# 468323_001_Connectors.net
KiCad netlist of a schematic drawn in Altium Designer
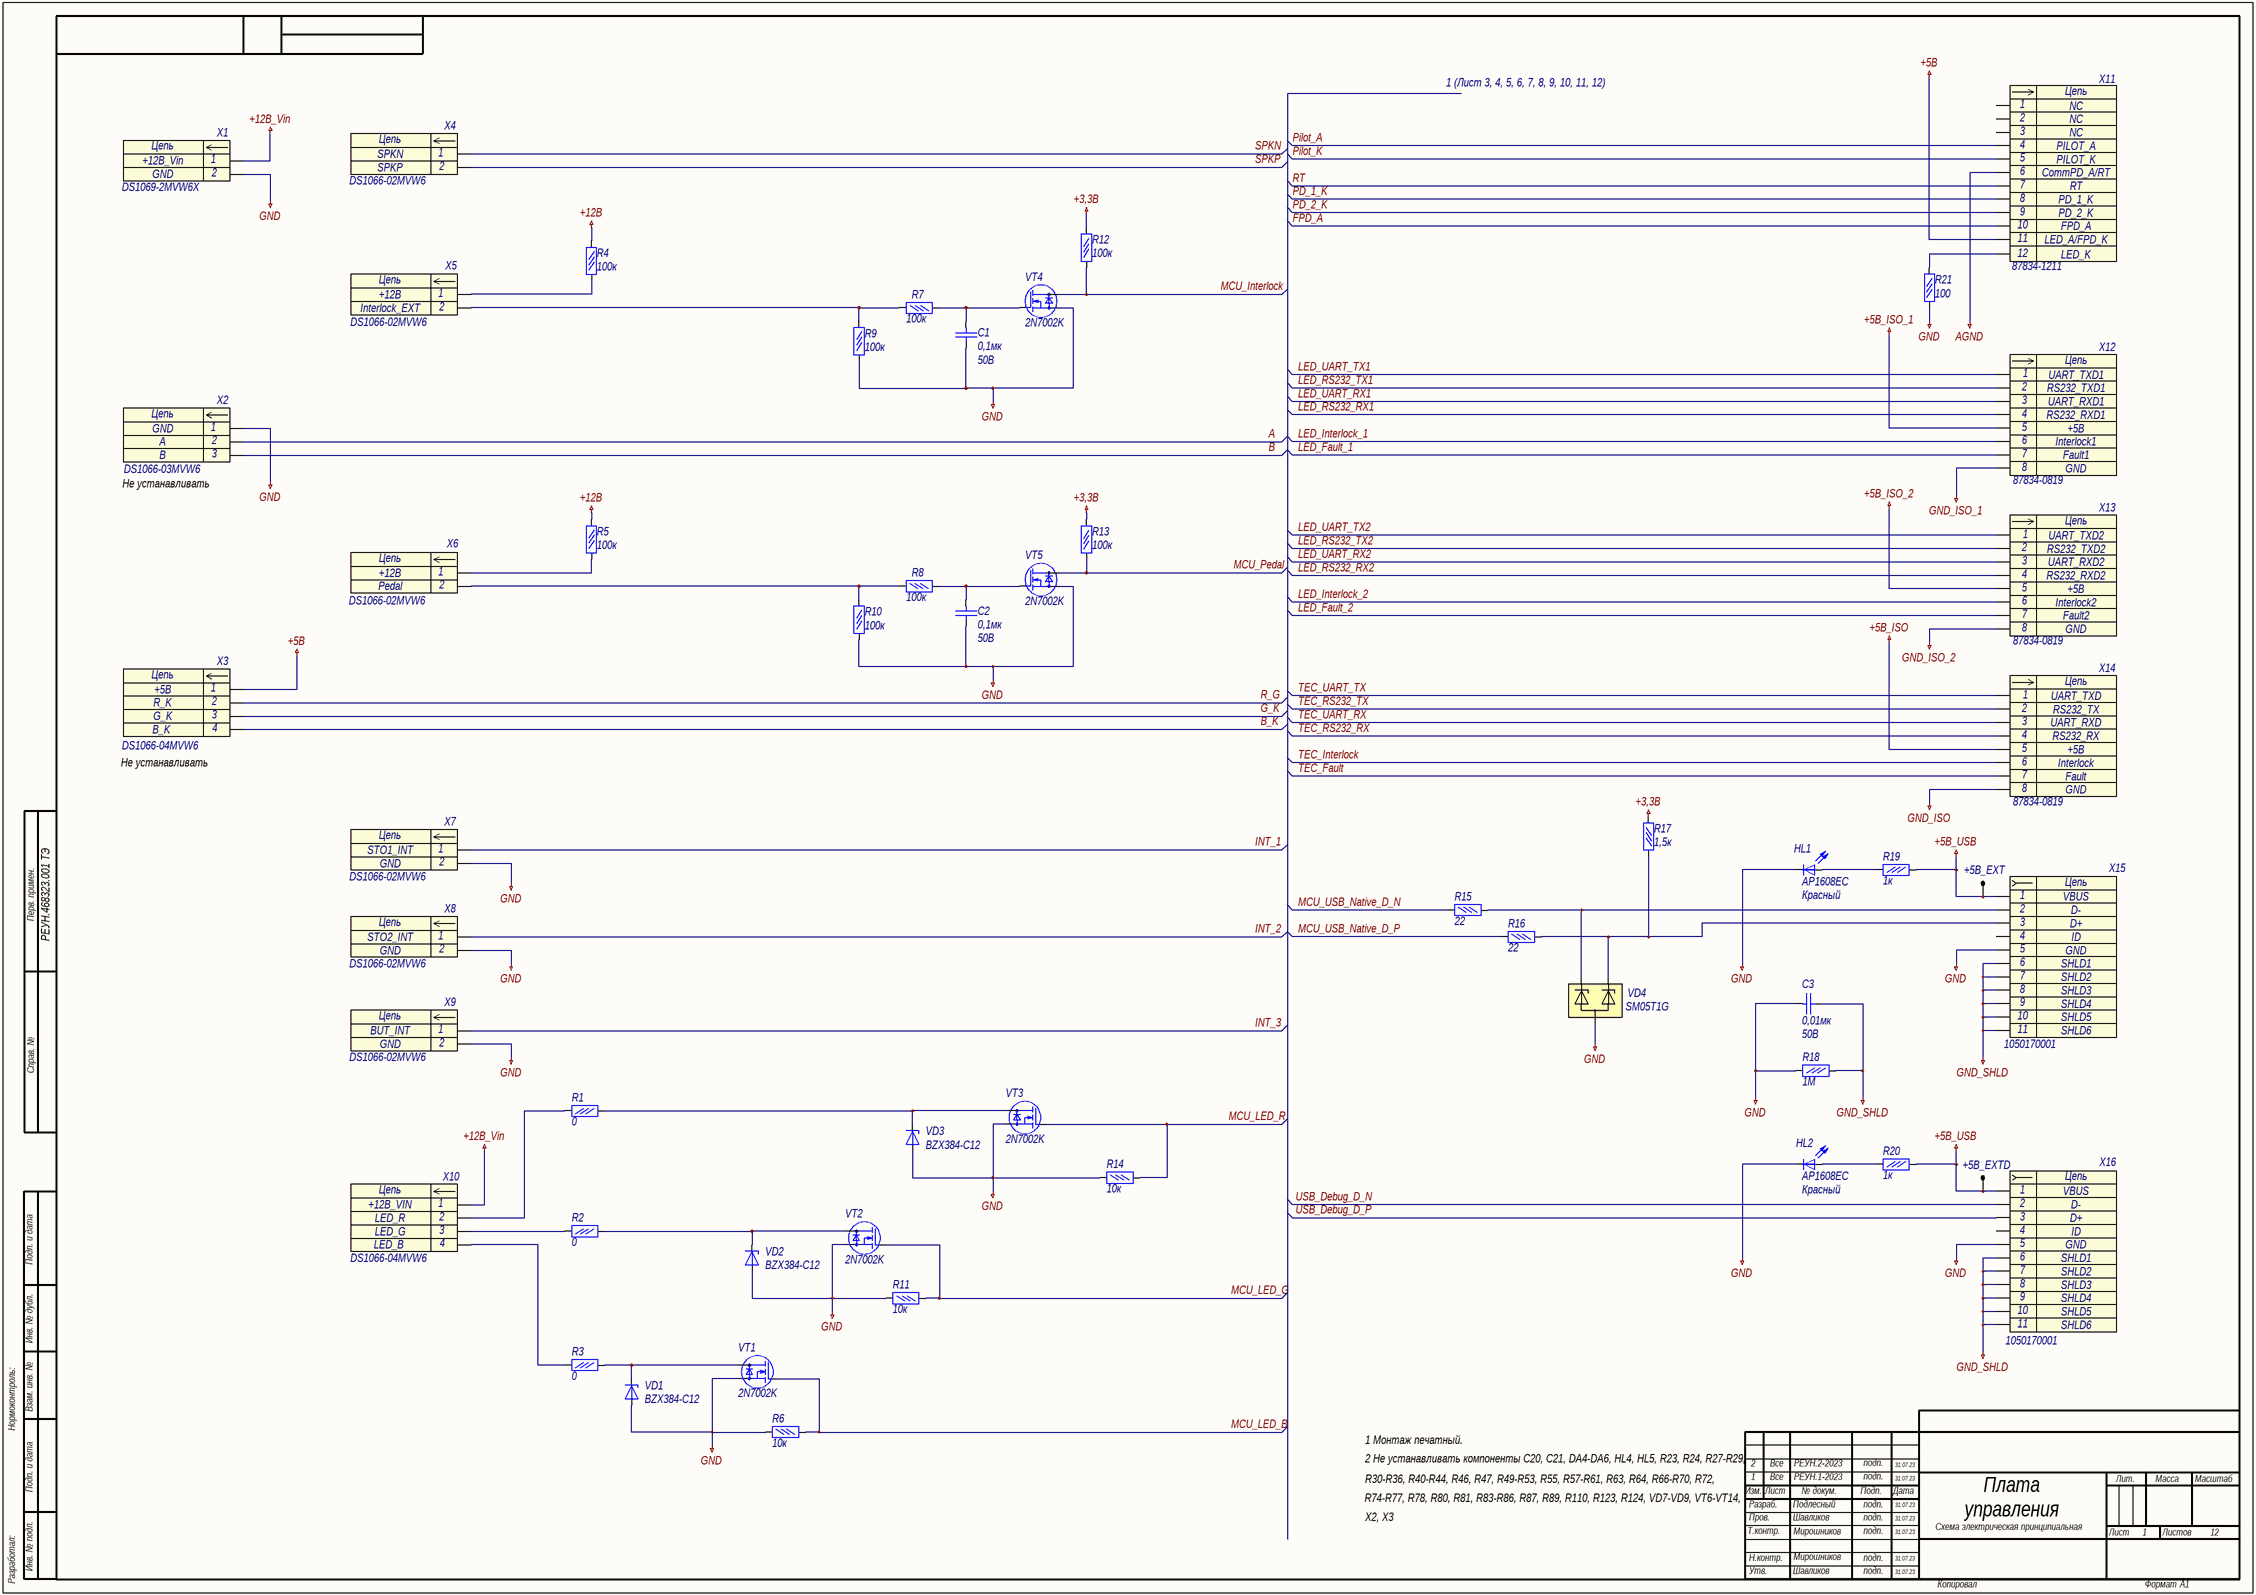
[diagram p0: РЕУН.468323.001_Connectors.SchDoc]

(export (version "E")
  (design (tool "Eeschema 10.0.6"))
  (components
    (comp (ref "+5В_EXT")
      (value "\"1\"")
      (footprint "0.5 x 1_round")
      (description "Test point")
      (libsource (lib "TarabusLib_KOR") (part "TestPoint"))
    )
    (comp (ref "+5В_EXTD")
      (value "\"1\"")
      (footprint "0.5 x 1_round")
      (description "Test point")
      (libsource (lib "TarabusLib_KOR") (part "TestPoint"))
    )
    (comp (ref "C1")
      (value "0,1мк")
      (footprint "C0805_AA")
      (description "Конденсатор кер.")
      (fields (field (name "VOLTAGE") "50В"))
      (libsource (lib "Library_Diana") (part "Конденсатор кер."))
    )
    (comp (ref "C2")
      (value "0,1мк")
      (footprint "C0805_AA")
      (description "Конденсатор кер.")
      (fields (field (name "VOLTAGE") "50В"))
      (libsource (lib "Library_Diana") (part "Конденсатор кер."))
    )
    (comp (ref "C3")
      (value "0,01мк")
      (footprint "C0805_AA")
      (description "Конденсатор кер.")
      (fields (field (name "VOLTAGE") "50В"))
      (libsource (lib "Library_Diana") (part "Конденсатор кер."))
    )
    (comp (ref "HL1")
      (value "AP1608EC")
      (description "Светодиод")
      (fields (field (name "NAME") "AP1608EC") (field (name "COLOR") "Красный"))
      (libsource (lib "Library_Diana") (part "led"))
    )
    (comp (ref "HL2")
      (value "AP1608EC")
      (description "Светодиод")
      (fields (field (name "NAME") "AP1608EC") (field (name "COLOR") "Красный"))
      (libsource (lib "Library_Diana") (part "led"))
    )
    (comp (ref "R1")
      (value "0")
      (footprint "R1206")
      (description "Резистор 0,05Вт")
      (libsource (lib "") (part "Резистор  0,05Вт_2"))
    )
    (comp (ref "R2")
      (value "0")
      (footprint "R1206")
      (description "Резистор 0,05Вт")
      (libsource (lib "") (part "Резистор  0,05Вт_2"))
    )
    (comp (ref "R3")
      (value "0")
      (footprint "R1206")
      (description "Резистор 0,05Вт")
      (libsource (lib "") (part "Резистор  0,05Вт_2"))
    )
    (comp (ref "R4")
      (value "100к")
      (footprint "R1206")
      (description "Резистор 0,05Вт")
      (libsource (lib "Library_Diana") (part "Резистор  0,05Вт"))
    )
    (comp (ref "R5")
      (value "100к")
      (footprint "R1206")
      (description "Резистор 0,05Вт")
      (libsource (lib "Library_Diana") (part "Резистор  0,05Вт"))
    )
    (comp (ref "R6")
      (value "10к")
      (footprint "R1206")
      (description "Резистор 0,05Вт")
      (libsource (lib "") (part "Резистор  0,05Вт_3"))
    )
    (comp (ref "R7")
      (value "100к")
      (footprint "R1206")
      (description "Резистор 0,05Вт")
      (libsource (lib "") (part "Резистор  0,05Вт_1"))
    )
    (comp (ref "R8")
      (value "100к")
      (footprint "R1206")
      (description "Резистор 0,05Вт")
      (libsource (lib "") (part "Резистор  0,05Вт_3"))
    )
    (comp (ref "R9")
      (value "100к")
      (footprint "R1206")
      (description "Резистор 0,05Вт")
      (libsource (lib "Library_Diana") (part "Резистор  0,05Вт"))
    )
    (comp (ref "R10")
      (value "100к")
      (footprint "R1206")
      (description "Резистор 0,05Вт")
      (libsource (lib "Library_Diana") (part "Резистор  0,05Вт"))
    )
    (comp (ref "R11")
      (value "10к")
      (footprint "R1206")
      (description "Резистор 0,05Вт")
      (libsource (lib "") (part "Резистор  0,05Вт_1"))
    )
    (comp (ref "R12")
      (value "100к")
      (footprint "R1206")
      (description "Резистор 0,05Вт")
      (libsource (lib "") (part "Резистор  0,05Вт_2"))
    )
    (comp (ref "R13")
      (value "100к")
      (footprint "R1206")
      (description "Резистор 0,05Вт")
      (libsource (lib "") (part "Резистор  0,05Вт_2"))
    )
    (comp (ref "R14")
      (value "10к")
      (footprint "R1206")
      (description "Резистор 0,05Вт")
      (libsource (lib "") (part "Резистор  0,05Вт_3"))
    )
    (comp (ref "R15")
      (value "22")
      (footprint "R1206")
      (description "Резистор 0,05Вт")
      (libsource (lib "") (part "Резистор  0,05Вт_3"))
    )
    (comp (ref "R16")
      (value "22")
      (footprint "R1206")
      (description "Резистор 0,05Вт")
      (libsource (lib "") (part "Резистор  0,05Вт_3"))
    )
    (comp (ref "R17")
      (value "1,5к")
      (footprint "R1206")
      (description "Резистор 0,05Вт")
      (libsource (lib "") (part "Резистор  0,05Вт_3"))
    )
    (comp (ref "R18")
      (value "1M")
      (footprint "R1206")
      (description "Резистор 0,05Вт")
      (libsource (lib "Library_Diana") (part "Резистор  0,05Вт"))
    )
    (comp (ref "R19")
      (value "1к")
      (footprint "R1206")
      (description "Резистор 0,05Вт")
      (libsource (lib "Library_Diana") (part "Резистор  0,05Вт"))
    )
    (comp (ref "R20")
      (value "1к")
      (footprint "R1206")
      (description "Резистор 0,05Вт")
      (libsource (lib "Library_Diana") (part "Резистор  0,05Вт"))
    )
    (comp (ref "R21")
      (value "100")
      (footprint "R1206")
      (description "Резистор 0,05Вт")
      (libsource (lib "") (part "Резистор  0,05Вт_2"))
    )
    (comp (ref "VD1")
      (value "BZX384-C12")
      (footprint "SOT23-2_A")
      (description "Стабилитрон")
      (libsource (lib "Library_Diana") (part "DiodeZener"))
    )
    (comp (ref "VD2")
      (value "BZX384-C12")
      (footprint "SOT23-2_A")
      (description "Стабилитрон")
      (libsource (lib "Library_Diana") (part "DiodeZener"))
    )
    (comp (ref "VD3")
      (value "BZX384-C12")
      (footprint "SOT23-2_A")
      (description "Стабилитрон")
      (libsource (lib "Library_Diana") (part "DiodeZener"))
    )
    (comp (ref "VD4")
      (value "SM05T1G")
      (description "Сборка TVS-диодов")
      (libsource (lib "Library_Diana") (part "ZenerArray2"))
    )
    (comp (ref "VT1")
      (value "2N7002K")
      (footprint "SOT:SOT23-3")
      (fields (field (name "NAME") "2N7002K"))
      (libsource (lib "Library_Diana") (part "mosfet-n"))
    )
    (comp (ref "VT2")
      (value "2N7002K")
      (footprint "SOT:SOT23-3")
      (fields (field (name "NAME") "2N7002K"))
      (libsource (lib "Library_Diana") (part "mosfet-n"))
    )
    (comp (ref "VT3")
      (value "2N7002K")
      (footprint "SOT:SOT23-3")
      (fields (field (name "NAME") "2N7002K"))
      (libsource (lib "Library_Diana") (part "mosfet-n"))
    )
    (comp (ref "VT4")
      (value "2N7002K")
      (footprint "SOT:SOT23-3")
      (fields (field (name "NAME") "2N7002K"))
      (libsource (lib "Library_Diana") (part "mosfet-n"))
    )
    (comp (ref "VT5")
      (value "2N7002K")
      (footprint "SOT:SOT23-3")
      (fields (field (name "NAME") "2N7002K"))
      (libsource (lib "Library_Diana") (part "mosfet-n"))
    )
    (comp (ref "X1")
      (value "DS1069-2MVW6X")
      (description "Разъем - 8 конт. вилка")
      (fields (field (name "NAME") "DS1069-2MVW6X"))
      (libsource (lib "Library_Diana") (part "x8-m_1"))
    )
    (comp (ref "X2")
      (value "DS1066-03MVW6")
      (description "Разъем - 8 конт. вилка")
      (fields (field (name "NAME") "DS1066-03MVW6"))
      (libsource (lib "Library_Diana") (part "x8-m_1_1"))
    )
    (comp (ref "X3")
      (value "DS1066-04MVW6")
      (description "Разъем - 8 конт. вилка")
      (fields (field (name "NAME") "DS1066-04MVW6"))
      (libsource (lib "Library_Diana") (part "x8-m_1_1_1"))
    )
    (comp (ref "X4")
      (value "DS1066-02MVW6")
      (description "Разъем - 8 конт. вилка")
      (fields (field (name "NAME") "DS1066-02MVW6"))
      (libsource (lib "Library_Diana") (part "x8-m_1"))
    )
    (comp (ref "X5")
      (value "DS1066-02MVW6")
      (description "Разъем - 8 конт. вилка")
      (fields (field (name "NAME") "DS1066-02MVW6"))
      (libsource (lib "Library_Diana") (part "x8-m_1"))
    )
    (comp (ref "X6")
      (value "DS1066-02MVW6")
      (description "Разъем - 8 конт. вилка")
      (fields (field (name "NAME") "DS1066-02MVW6"))
      (libsource (lib "Library_Diana") (part "x8-m_1"))
    )
    (comp (ref "X7")
      (value "DS1066-02MVW6")
      (description "Разъем - 8 конт. вилка")
      (fields (field (name "NAME") "DS1066-02MVW6"))
      (libsource (lib "Library_Diana") (part "x8-m_1"))
    )
    (comp (ref "X8")
      (value "DS1066-02MVW6")
      (description "Разъем - 8 конт. вилка")
      (fields (field (name "NAME") "DS1066-02MVW6"))
      (libsource (lib "Library_Diana") (part "x8-m_1"))
    )
    (comp (ref "X9")
      (value "DS1066-02MVW6")
      (description "Разъем - 8 конт. вилка")
      (fields (field (name "NAME") "DS1066-02MVW6"))
      (libsource (lib "Library_Diana") (part "x8-m_1"))
    )
    (comp (ref "X10")
      (value "DS1066-04MVW6")
      (description "Разъем - 8 конт. вилка")
      (fields (field (name "NAME") "DS1066-04MVW6"))
      (libsource (lib "Library_Diana") (part "x8-m_1_1_1"))
    )
    (comp (ref "X11")
      (value "87834-1211")
      (description "Разъем - 10 конт. вилка")
      (fields (field (name "NAME") "87834-1211"))
      (libsource (lib "Library_Diana") (part "x10-m_1_1"))
    )
    (comp (ref "X12")
      (value "87834-0819")
      (description "Разъем - 8 конт. вилка")
      (fields (field (name "NAME") "87834-0819"))
      (libsource (lib "Library_Diana") (part "x8-m"))
    )
    (comp (ref "X13")
      (value "87834-0819")
      (description "Разъем - 8 конт. вилка")
      (fields (field (name "NAME") "87834-0819"))
      (libsource (lib "Library_Diana") (part "x8-m"))
    )
    (comp (ref "X14")
      (value "87834-0819")
      (description "Разъем - 8 конт. вилка")
      (fields (field (name "NAME") "87834-0819"))
      (libsource (lib "Library_Diana") (part "x8-m"))
    )
    (comp (ref "X15")
      (value "1050170001")
      (description "Разъем - 10 конт. вилка")
      (fields (field (name "NAME") "1050170001"))
      (libsource (lib "Library_Diana") (part "x10-m_1"))
    )
    (comp (ref "X16")
      (value "1050170001")
      (description "Разъем - 10 конт. вилка")
      (fields (field (name "NAME") "1050170001"))
      (libsource (lib "Library_Diana") (part "x10-m_1"))
    )
  )
  (nets
    (net (code "1") (name "+3,3В") (class "Default")
      (node (ref "R12") (pin "1") (pinfunction "1_1") (pintype "passive"))
      (node (ref "R13") (pin "1") (pinfunction "1_1") (pintype "passive"))
      (node (ref "R17") (pin "2") (pinfunction "2_2") (pintype "passive"))
    )
    (net (code "2") (name "+5В") (class "Default")
      (node (ref "X11") (pin "10") (pinfunction "10_10") (pintype "passive"))
      (node (ref "X3") (pin "1") (pinfunction "1_1") (pintype "passive"))
    )
    (net (code "3") (name "+5В_ISO") (class "Default")
      (node (ref "X14") (pin "5") (pinfunction "5_5") (pintype "passive"))
    )
    (net (code "4") (name "+5В_ISO_1") (class "Default")
      (node (ref "X12") (pin "5") (pinfunction "5_5") (pintype "passive"))
    )
    (net (code "5") (name "+5В_ISO_2") (class "Default")
      (node (ref "X13") (pin "5") (pinfunction "5_5") (pintype "passive"))
    )
    (net (code "6") (name "+5В_USB") (class "Default")
      (node (ref "+5В_EXT") (pin "1") (pinfunction "1_1") (pintype "passive"))
      (node (ref "+5В_EXTD") (pin "1") (pinfunction "1_1") (pintype "passive"))
      (node (ref "R19") (pin "2") (pinfunction "2_2") (pintype "passive"))
      (node (ref "R20") (pin "2") (pinfunction "2_2") (pintype "passive"))
      (node (ref "X15") (pin "1") (pinfunction "1_1") (pintype "passive"))
      (node (ref "X16") (pin "1") (pinfunction "1_1") (pintype "passive"))
    )
    (net (code "7") (name "+12В") (class "Default")
      (node (ref "R4") (pin "2") (pinfunction "2_2") (pintype "passive"))
      (node (ref "R5") (pin "2") (pinfunction "2_2") (pintype "passive"))
    )
    (net (code "8") (name "+12В_Vin") (class "Default")
      (node (ref "X1") (pin "1") (pinfunction "1_1") (pintype "passive"))
      (node (ref "X10") (pin "1") (pinfunction "1_1") (pintype "passive"))
    )
    (net (code "9") (name "/A") (class "Default")
      (node (ref "X2") (pin "2") (pinfunction "2_2") (pintype "passive"))
    )
    (net (code "10") (name "/B") (class "Default")
      (node (ref "X2") (pin "2") (pinfunction "2_2") (pintype "passive"))
    )
    (net (code "11") (name "/B_K") (class "Default")
      (node (ref "X3") (pin "2") (pinfunction "2_2") (pintype "passive"))
    )
    (net (code "12") (name "/FPD_A") (class "Default")
      (node (ref "X11") (pin "10") (pinfunction "10_10") (pintype "passive"))
    )
    (net (code "13") (name "/G_K") (class "Default")
      (node (ref "X3") (pin "2") (pinfunction "2_2") (pintype "passive"))
    )
    (net (code "14") (name "/INT_1") (class "Default")
      (node (ref "X7") (pin "1") (pinfunction "1_1") (pintype "passive"))
    )
    (net (code "15") (name "/INT_2") (class "Default")
      (node (ref "X8") (pin "1") (pinfunction "1_1") (pintype "passive"))
    )
    (net (code "16") (name "/INT_3") (class "Default")
      (node (ref "X9") (pin "1") (pinfunction "1_1") (pintype "passive"))
    )
    (net (code "17") (name "/LED_Fault_1") (class "Default")
      (node (ref "X12") (pin "7") (pinfunction "7_7") (pintype "passive"))
    )
    (net (code "18") (name "/LED_Fault_2") (class "Default")
      (node (ref "X13") (pin "7") (pinfunction "7_7") (pintype "passive"))
    )
    (net (code "19") (name "/LED_Interlock_1") (class "Default")
      (node (ref "X12") (pin "6") (pinfunction "6_6") (pintype "passive"))
    )
    (net (code "20") (name "/LED_Interlock_2") (class "Default")
      (node (ref "X13") (pin "6") (pinfunction "6_6") (pintype "passive"))
    )
    (net (code "21") (name "/LED_RS232_RX1") (class "Default")
      (node (ref "X12") (pin "4") (pinfunction "4_4") (pintype "passive"))
    )
    (net (code "22") (name "/LED_RS232_RX2") (class "Default")
      (node (ref "X13") (pin "4") (pinfunction "4_4") (pintype "passive"))
    )
    (net (code "23") (name "/LED_RS232_TX1") (class "Default")
      (node (ref "X12") (pin "2") (pinfunction "2_2") (pintype "passive"))
    )
    (net (code "24") (name "/LED_RS232_TX2") (class "Default")
      (node (ref "X13") (pin "2") (pinfunction "2_2") (pintype "passive"))
    )
    (net (code "25") (name "/LED_UART_RX1") (class "Default")
      (node (ref "X12") (pin "3") (pinfunction "3_3") (pintype "passive"))
    )
    (net (code "26") (name "/LED_UART_RX2") (class "Default")
      (node (ref "X13") (pin "3") (pinfunction "3_3") (pintype "passive"))
    )
    (net (code "27") (name "/LED_UART_TX1") (class "Default")
      (node (ref "X12") (pin "1") (pinfunction "1_1") (pintype "passive"))
    )
    (net (code "28") (name "/LED_UART_TX2") (class "Default")
      (node (ref "X13") (pin "1") (pinfunction "1_1") (pintype "passive"))
    )
    (net (code "29") (name "/MCU_Interlock") (class "Default")
      (node (ref "R12") (pin "2") (pinfunction "2_2") (pintype "passive"))
      (node (ref "VT4") (pin "3") (pinfunction "D_3") (pintype "passive"))
    )
    (net (code "30") (name "/MCU_LED_B") (class "Default")
      (node (ref "R6") (pin "2") (pinfunction "2_2") (pintype "passive"))
      (node (ref "VT1") (pin "1") (pinfunction "G_1") (pintype "passive"))
    )
    (net (code "31") (name "/MCU_LED_G") (class "Default")
      (node (ref "R11") (pin "1") (pinfunction "1_1") (pintype "passive"))
      (node (ref "VT2") (pin "1") (pinfunction "G_1") (pintype "passive"))
    )
    (net (code "32") (name "/MCU_LED_R") (class "Default")
      (node (ref "R14") (pin "2") (pinfunction "2_2") (pintype "passive"))
      (node (ref "VT3") (pin "1") (pinfunction "G_1") (pintype "passive"))
    )
    (net (code "33") (name "/MCU_Pedal") (class "Default")
      (node (ref "R13") (pin "2") (pinfunction "2_2") (pintype "passive"))
      (node (ref "VT5") (pin "3") (pinfunction "D_3") (pintype "passive"))
    )
    (net (code "34") (name "/MCU_USB_Native_D_N") (class "Default")
      (node (ref "R15") (pin "1") (pinfunction "1_1") (pintype "passive"))
    )
    (net (code "35") (name "/MCU_USB_Native_D_P") (class "Default")
      (node (ref "R16") (pin "1") (pinfunction "1_1") (pintype "passive"))
    )
    (net (code "36") (name "/PD_1_K") (class "Default")
      (node (ref "X11") (pin "8") (pinfunction "8_8") (pintype "passive"))
    )
    (net (code "37") (name "/PD_2_K") (class "Default")
      (node (ref "X11") (pin "9") (pinfunction "9_9") (pintype "passive"))
    )
    (net (code "38") (name "/Pilot_A") (class "Default")
      (node (ref "X11") (pin "4") (pinfunction "4_4") (pintype "passive"))
    )
    (net (code "39") (name "/Pilot_K") (class "Default")
      (node (ref "X11") (pin "5") (pinfunction "5_5") (pintype "passive"))
    )
    (net (code "40") (name "/RT") (class "Default")
      (node (ref "X11") (pin "7") (pinfunction "7_7") (pintype "passive"))
    )
    (net (code "41") (name "/R_G") (class "Default")
      (node (ref "X3") (pin "2") (pinfunction "2_2") (pintype "passive"))
    )
    (net (code "42") (name "/SPKN") (class "Default")
      (node (ref "X4") (pin "1") (pinfunction "1_1") (pintype "passive"))
    )
    (net (code "43") (name "/SPKP") (class "Default")
      (node (ref "X4") (pin "2") (pinfunction "2_2") (pintype "passive"))
    )
    (net (code "44") (name "/TEC_Fault") (class "Default")
      (node (ref "X14") (pin "7") (pinfunction "7_7") (pintype "passive"))
    )
    (net (code "45") (name "/TEC_Interlock") (class "Default")
      (node (ref "X14") (pin "6") (pinfunction "6_6") (pintype "passive"))
    )
    (net (code "46") (name "/TEC_RS232_RX") (class "Default")
      (node (ref "X14") (pin "4") (pinfunction "4_4") (pintype "passive"))
    )
    (net (code "47") (name "/TEC_RS232_TX") (class "Default")
      (node (ref "X14") (pin "2") (pinfunction "2_2") (pintype "passive"))
    )
    (net (code "48") (name "/TEC_UART_RX") (class "Default")
      (node (ref "X14") (pin "3") (pinfunction "3_3") (pintype "passive"))
    )
    (net (code "49") (name "/TEC_UART_TX") (class "Default")
      (node (ref "X14") (pin "1") (pinfunction "1_1") (pintype "passive"))
    )
    (net (code "50") (name "/USB_Debug_D_N") (class "Default")
      (node (ref "X16") (pin "2") (pinfunction "2_2") (pintype "passive"))
    )
    (net (code "51") (name "/USB_Debug_D_P") (class "Default")
      (node (ref "X16") (pin "3") (pinfunction "3_3") (pintype "passive"))
    )
    (net (code "52") (name "AGND") (class "Default")
      (node (ref "X11") (pin "6") (pinfunction "6_6") (pintype "passive"))
    )
    (net (code "53") (name "GND") (class "Default")
      (node (ref "C1") (pin "1") (pinfunction "1_1") (pintype "passive"))
      (node (ref "C2") (pin "1") (pinfunction "1_1") (pintype "passive"))
      (node (ref "C3") (pin "2") (pinfunction "2_2") (pintype "passive"))
      (node (ref "HL1") (pin "2") (pinfunction "K_2") (pintype "passive"))
      (node (ref "HL2") (pin "2") (pinfunction "K_2") (pintype "passive"))
      (node (ref "R10") (pin "1") (pinfunction "1_1") (pintype "passive"))
      (node (ref "R11") (pin "2") (pinfunction "2_2") (pintype "passive"))
      (node (ref "R14") (pin "1") (pinfunction "1_1") (pintype "passive"))
      (node (ref "R18") (pin "1") (pinfunction "1_1") (pintype "passive"))
      (node (ref "R21") (pin "2") (pinfunction "2_2") (pintype "passive"))
      (node (ref "R6") (pin "1") (pinfunction "1_1") (pintype "passive"))
      (node (ref "R9") (pin "1") (pinfunction "1_1") (pintype "passive"))
      (node (ref "VD1") (pin "2") (pinfunction "A_2") (pintype "passive"))
      (node (ref "VD2") (pin "2") (pinfunction "A_2") (pintype "passive"))
      (node (ref "VD3") (pin "2") (pinfunction "A_2") (pintype "passive"))
      (node (ref "VD4") (pin "3") (pintype "passive"))
      (node (ref "VT1") (pin "2") (pinfunction "S_2") (pintype "passive"))
      (node (ref "VT2") (pin "2") (pinfunction "S_2") (pintype "passive"))
      (node (ref "VT3") (pin "2") (pinfunction "S_2") (pintype "passive"))
      (node (ref "VT4") (pin "2") (pinfunction "S_2") (pintype "passive"))
      (node (ref "VT5") (pin "2") (pinfunction "S_2") (pintype "passive"))
      (node (ref "X1") (pin "2") (pinfunction "2_2") (pintype "passive"))
      (node (ref "X15") (pin "5") (pinfunction "5_5") (pintype "passive"))
      (node (ref "X16") (pin "5") (pinfunction "5_5") (pintype "passive"))
      (node (ref "X2") (pin "1") (pinfunction "1_1") (pintype "passive"))
      (node (ref "X7") (pin "2") (pinfunction "2_2") (pintype "passive"))
      (node (ref "X8") (pin "2") (pinfunction "2_2") (pintype "passive"))
      (node (ref "X9") (pin "2") (pinfunction "2_2") (pintype "passive"))
    )
    (net (code "54") (name "GND_ISO") (class "Default")
      (node (ref "X14") (pin "8") (pinfunction "8_8") (pintype "passive"))
    )
    (net (code "55") (name "GND_ISO_1") (class "Default")
      (node (ref "X12") (pin "8") (pinfunction "8_8") (pintype "passive"))
    )
    (net (code "56") (name "GND_ISO_2") (class "Default")
      (node (ref "X13") (pin "8") (pinfunction "8_8") (pintype "passive"))
    )
    (net (code "57") (name "GND_SHLD") (class "Default")
      (node (ref "C3") (pin "1") (pinfunction "1_1") (pintype "passive"))
      (node (ref "R18") (pin "2") (pinfunction "2_2") (pintype "passive"))
      (node (ref "X15") (pin "10") (pinfunction "10_10") (pintype "passive"))
      (node (ref "X15") (pin "6") (pinfunction "6_6") (pintype "passive"))
      (node (ref "X15") (pin "7") (pinfunction "7_7") (pintype "passive"))
      (node (ref "X15") (pin "8") (pinfunction "8_8") (pintype "passive"))
      (node (ref "X15") (pin "9") (pinfunction "9_9") (pintype "passive"))
      (node (ref "X16") (pin "10") (pinfunction "10_10") (pintype "passive"))
      (node (ref "X16") (pin "6") (pinfunction "6_6") (pintype "passive"))
      (node (ref "X16") (pin "7") (pinfunction "7_7") (pintype "passive"))
      (node (ref "X16") (pin "8") (pinfunction "8_8") (pintype "passive"))
      (node (ref "X16") (pin "9") (pinfunction "9_9") (pintype "passive"))
    )
    (net (code "58") (name "Net-(HL1-A)") (class "Default")
      (node (ref "HL1") (pin "1") (pinfunction "A_1") (pintype "passive"))
      (node (ref "R19") (pin "1") (pinfunction "1_1") (pintype "passive"))
    )
    (net (code "59") (name "Net-(HL2-A)") (class "Default")
      (node (ref "HL2") (pin "1") (pinfunction "A_1") (pintype "passive"))
      (node (ref "R20") (pin "1") (pinfunction "1_1") (pintype "passive"))
    )
    (net (code "60") (name "Net-(R1-Pad2)") (class "Default")
      (node (ref "R1") (pin "2") (pinfunction "2_2") (pintype "passive"))
      (node (ref "X10") (pin "2") (pinfunction "2_2") (pintype "passive"))
    )
    (net (code "61") (name "Net-(R2-Pad2)") (class "Default")
      (node (ref "R2") (pin "2") (pinfunction "2_2") (pintype "passive"))
      (node (ref "X10") (pin "2") (pinfunction "2_2") (pintype "passive"))
    )
    (net (code "62") (name "Net-(R3-Pad2)") (class "Default")
      (node (ref "R3") (pin "2") (pinfunction "2_2") (pintype "passive"))
      (node (ref "X10") (pin "2") (pinfunction "2_2") (pintype "passive"))
    )
    (net (code "63") (name "Net-(R4-Pad1)") (class "Default")
      (node (ref "R4") (pin "1") (pinfunction "1_1") (pintype "passive"))
      (node (ref "X5") (pin "1") (pinfunction "1_1") (pintype "passive"))
    )
    (net (code "64") (name "Net-(R5-Pad1)") (class "Default")
      (node (ref "R5") (pin "1") (pinfunction "1_1") (pintype "passive"))
      (node (ref "X6") (pin "1") (pinfunction "1_1") (pintype "passive"))
    )
    (net (code "65") (name "Net-(R7-Pad2)") (class "Default")
      (node (ref "R7") (pin "2") (pinfunction "2_2") (pintype "passive"))
      (node (ref "R9") (pin "2") (pinfunction "2_2") (pintype "passive"))
      (node (ref "X5") (pin "2") (pinfunction "2_2") (pintype "passive"))
    )
    (net (code "66") (name "Net-(R10-Pad2)") (class "Default")
      (node (ref "R10") (pin "2") (pinfunction "2_2") (pintype "passive"))
      (node (ref "R8") (pin "1") (pinfunction "1_1") (pintype "passive"))
      (node (ref "X6") (pin "2") (pinfunction "2_2") (pintype "passive"))
    )
    (net (code "67") (name "Net-(R15-Pad2)") (class "Default")
      (node (ref "R15") (pin "2") (pinfunction "2_2") (pintype "passive"))
      (node (ref "VD4") (pin "1") (pintype "passive"))
      (node (ref "X15") (pin "2") (pinfunction "2_2") (pintype "passive"))
    )
    (net (code "68") (name "Net-(R16-Pad2)") (class "Default")
      (node (ref "R16") (pin "2") (pinfunction "2_2") (pintype "passive"))
      (node (ref "R17") (pin "1") (pinfunction "1_1") (pintype "passive"))
      (node (ref "VD4") (pin "2") (pintype "passive"))
      (node (ref "X15") (pin "3") (pinfunction "3_3") (pintype "passive"))
    )
    (net (code "69") (name "Net-(R21-Pad1)") (class "Default")
      (node (ref "R21") (pin "1") (pinfunction "1_1") (pintype "passive"))
      (node (ref "X11") (pin "10") (pinfunction "10_10") (pintype "passive"))
    )
    (net (code "70") (name "Net-(VD1-K)") (class "Default")
      (node (ref "R3") (pin "1") (pinfunction "1_1") (pintype "passive"))
      (node (ref "VD1") (pin "1") (pinfunction "K_1") (pintype "passive"))
      (node (ref "VT1") (pin "3") (pinfunction "D_3") (pintype "passive"))
    )
    (net (code "71") (name "Net-(VD2-K)") (class "Default")
      (node (ref "R2") (pin "1") (pinfunction "1_1") (pintype "passive"))
      (node (ref "VD2") (pin "1") (pinfunction "K_1") (pintype "passive"))
      (node (ref "VT2") (pin "3") (pinfunction "D_3") (pintype "passive"))
    )
    (net (code "72") (name "Net-(VD3-K)") (class "Default")
      (node (ref "R1") (pin "1") (pinfunction "1_1") (pintype "passive"))
      (node (ref "VD3") (pin "1") (pinfunction "K_1") (pintype "passive"))
      (node (ref "VT3") (pin "3") (pinfunction "D_3") (pintype "passive"))
    )
    (net (code "73") (name "Net-(VT4-G)") (class "Default")
      (node (ref "C1") (pin "2") (pinfunction "2_2") (pintype "passive"))
      (node (ref "R7") (pin "1") (pinfunction "1_1") (pintype "passive"))
      (node (ref "VT4") (pin "1") (pinfunction "G_1") (pintype "passive"))
    )
    (net (code "74") (name "Net-(VT5-G)") (class "Default")
      (node (ref "C2") (pin "2") (pinfunction "2_2") (pintype "passive"))
      (node (ref "R8") (pin "2") (pinfunction "2_2") (pintype "passive"))
      (node (ref "VT5") (pin "1") (pinfunction "G_1") (pintype "passive"))
    )
    (net (code "75") (name "unconnected-(X11-Pad1)") (class "Default")
      (node (ref "X11") (pin "1") (pinfunction "1_1") (pintype "passive"))
    )
    (net (code "76") (name "unconnected-(X11-Pad2)") (class "Default")
      (node (ref "X11") (pin "2") (pinfunction "2_2") (pintype "passive"))
    )
    (net (code "77") (name "unconnected-(X11-Pad3)") (class "Default")
      (node (ref "X11") (pin "3") (pinfunction "3_3") (pintype "passive"))
    )
    (net (code "78") (name "unconnected-(X15-Pad4)") (class "Default")
      (node (ref "X15") (pin "4") (pinfunction "4_4") (pintype "passive"))
    )
    (net (code "79") (name "unconnected-(X16-Pad4)") (class "Default")
      (node (ref "X16") (pin "4") (pinfunction "4_4") (pintype "passive"))
    )
  )
)
